# Arduino_Connector.net
KiCad netlist of a schematic drawn in Altium Designer
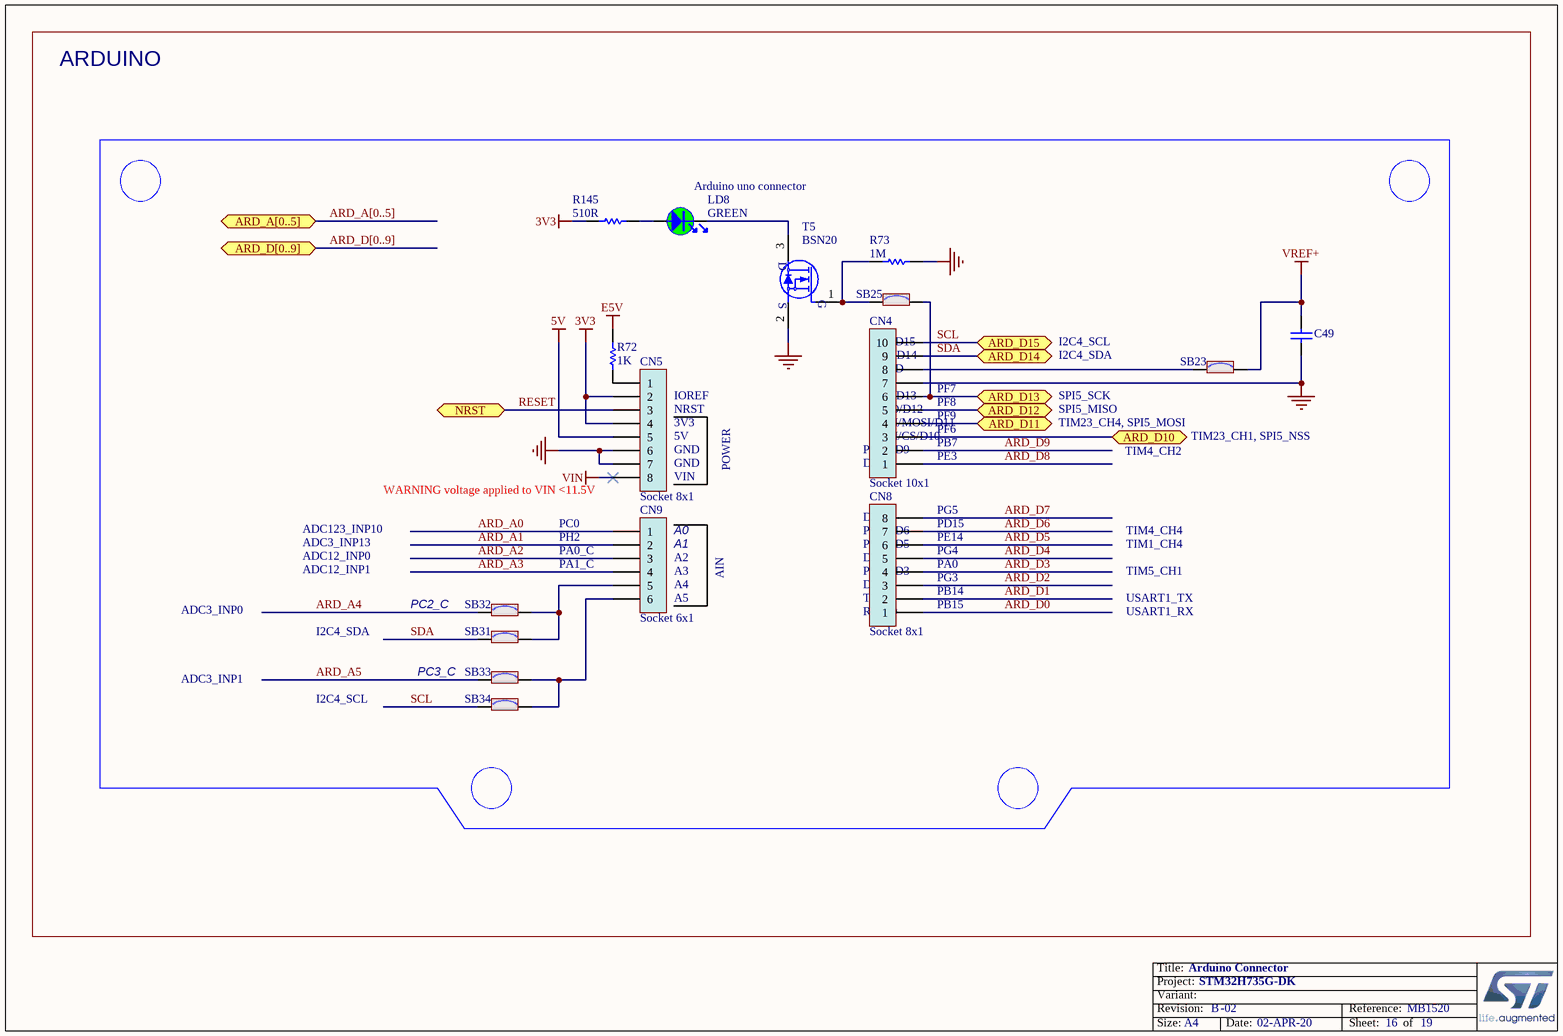
[diagram p0: Arduino Connector.SchDoc]

(export (version "E")
  (design (tool "Eeschema 10.0.6"))
  (components
    (comp (ref "C49")
      (value "Capacitor")
      (footprint "C0603")
      (description "Capacitor, MLCC, 100nF, 16V, X7R, 10%, 0603, T=0,8mm")
      (fields
        (field (name "INTERNAL_PART_NUMBER") "MCD-00211")
        (field (name "MANUFACTURER_PART_NUMBER") "CC0603KRX7R7BB104")
        (field (name "PROVIDED_BY") "SUBCO")
      )
      (libsource (lib "MCD_PARTS_database") (part "Capacitor"))
    )
    (comp (ref "CN4")
      (value "Socket 10x1")
      (footprint "CON_SAMTEC_SSW-110-22-X-S-VS")
      (description "Socket, 10x1, 2.54mm, VR, SMT, Height 9.78mm")
      (fields
        (field (name "INTERNAL_PART_NUMBER") "MCD-00301")
        (field (name "MANUFACTURER_PART_NUMBER") "SSW-110-22-L-S-VS")
        (field (name "PROVIDED_BY") "SUBCO")
      )
      (libsource (lib "MCD_PARTS_database") (part "Socket 10x1"))
    )
    (comp (ref "CN5")
      (value "Socket 8x1")
      (footprint "CON_SAMTEC_SSW-108-22-X-S-VS")
      (description "Socket, 8x1, 2.54mm, VR, SMT, Height 9.78mm")
      (fields
        (field (name "INTERNAL_PART_NUMBER") "MCD-00300")
        (field (name "MANUFACTURER_PART_NUMBER") "SSW-108-22-L-S-VS")
        (field (name "PROVIDED_BY") "SUBCO")
      )
      (libsource (lib "MCD_PARTS_database") (part "Socket 8x1"))
    )
    (comp (ref "CN8")
      (value "Socket 8x1")
      (footprint "CON_SAMTEC_SSW-108-22-X-S-VS")
      (description "Socket, 8x1, 2.54mm, VR, SMT, Height 9.78mm")
      (fields
        (field (name "INTERNAL_PART_NUMBER") "MCD-00300")
        (field (name "MANUFACTURER_PART_NUMBER") "SSW-108-22-L-S-VS")
        (field (name "PROVIDED_BY") "SUBCO")
      )
      (libsource (lib "") (part "Socket 8x1_1"))
    )
    (comp (ref "CN9")
      (value "Socket 6x1")
      (footprint "CON_SAMTEC_SSW-106-22-X-S-VS")
      (description "Socket, 6x1, 2.54mm, VR, SMT, Height 9.78mm")
      (fields
        (field (name "INTERNAL_PART_NUMBER") "MCD-00299")
        (field (name "MANUFACTURER_PART_NUMBER") "SSW-106-22-L-S-VS")
        (field (name "PROVIDED_BY") "SUBCO")
      )
      (libsource (lib "MCD_PARTS_database") (part "Socket 6x1"))
    )
    (comp (ref "LD8")
      (value "GREEN")
      (footprint "LED_0603_GREEN")
      (description "LED, Green, 0603")
      (fields
        (field (name "INTERNAL_PART_NUMBER") "MCD-00050")
        (field (name "MANUFACTURER_PART_NUMBER") "19-213SYGC/S530-E2/TR8")
        (field (name "PROVIDED_BY") "SUBCO")
      )
      (libsource (lib "MCD_PARTS_database") (part "LED_green"))
    )
    (comp (ref "R72")
      (value "1K")
      (footprint "R0603")
      (description "Resistor,1K,0603,1%,1/10W")
      (fields
        (field (name "INTERNAL_PART_NUMBER") "MCD-00070")
        (field (name "MANUFACTURER_PART_NUMBER") "RC0603FR-071KL")
        (field (name "PROVIDED_BY") "SUBCO")
      )
      (libsource (lib "MCD_PARTS_database") (part "Resistor"))
    )
    (comp (ref "R73")
      (value "1M")
      (footprint "R0603")
      (description "Resistor,1M,0603,1%,1/10W")
      (fields
        (field (name "INTERNAL_PART_NUMBER") "MCD-00257")
        (field (name "MANUFACTURER_PART_NUMBER") "RC0603FR-071ML")
        (field (name "PROVIDED_BY") "SUBCO")
      )
      (libsource (lib "MCD_PARTS_database") (part "Resistor"))
    )
    (comp (ref "R145")
      (value "510R")
      (footprint "R0603")
      (description "Resistor,510R,0603,1%,1/10W")
      (fields
        (field (name "INTERNAL_PART_NUMBER") "MCD-00225")
        (field (name "MANUFACTURER_PART_NUMBER") "RC0603FR-07510RL")
        (field (name "PROVIDED_BY") "SUBCO")
      )
      (libsource (lib "MCD_PARTS_database") (part "Resistor"))
    )
    (comp (ref "SB23")
      (value "SB_ON")
      (footprint "SOLDER-BRIDGE_R0603-0R")
      (description "Solder Bridge ON")
      (fields
        (field (name "INTERNAL_PART_NUMBER") "MCD-00071")
        (field (name "MANUFACTURER_PART_NUMBER") "RC0603JR-070RL")
        (field (name "PROVIDED_BY") "SUBCO")
      )
      (libsource (lib "MCD_PARTS_database") (part "SB_ON"))
    )
    (comp (ref "SB25")
      (value "SB_ON")
      (footprint "SOLDER-BRIDGE_R0603-0R")
      (description "Solder Bridge ON")
      (fields
        (field (name "INTERNAL_PART_NUMBER") "MCD-00071")
        (field (name "MANUFACTURER_PART_NUMBER") "RC0603JR-070RL")
        (field (name "PROVIDED_BY") "SUBCO")
      )
      (libsource (lib "MCD_PARTS_database") (part "SB_ON"))
    )
    (comp (ref "SB31")
      (value "SB_ON")
      (footprint "SOLDER-BRIDGE_R0603-0R")
      (description "Solder Bridge ON")
      (fields
        (field (name "INTERNAL_PART_NUMBER") "MCD-00071")
        (field (name "MANUFACTURER_PART_NUMBER") "RC0603JR-070RL")
        (field (name "PROVIDED_BY") "SUBCO")
      )
      (libsource (lib "MCD_PARTS_database") (part "SB_ON"))
    )
    (comp (ref "SB32")
      (value "SB_ON")
      (footprint "SOLDER-BRIDGE_R0603-0R")
      (description "Solder Bridge ON")
      (fields
        (field (name "INTERNAL_PART_NUMBER") "MCD-00071")
        (field (name "MANUFACTURER_PART_NUMBER") "RC0603JR-070RL")
        (field (name "PROVIDED_BY") "SUBCO")
      )
      (libsource (lib "MCD_PARTS_database") (part "SB_ON"))
    )
    (comp (ref "SB33")
      (value "SB_ON")
      (footprint "SOLDER-BRIDGE_R0603-0R")
      (description "Solder Bridge ON")
      (fields
        (field (name "INTERNAL_PART_NUMBER") "MCD-00071")
        (field (name "MANUFACTURER_PART_NUMBER") "RC0603JR-070RL")
        (field (name "PROVIDED_BY") "SUBCO")
      )
      (libsource (lib "MCD_PARTS_database") (part "SB_ON"))
    )
    (comp (ref "SB34")
      (value "SB_ON")
      (footprint "SOLDER-BRIDGE_R0603-0R")
      (description "Solder Bridge ON")
      (fields
        (field (name "INTERNAL_PART_NUMBER") "MCD-00071")
        (field (name "MANUFACTURER_PART_NUMBER") "RC0603JR-070RL")
        (field (name "PROVIDED_BY") "SUBCO")
      )
      (libsource (lib "MCD_PARTS_database") (part "SB_ON"))
    )
    (comp (ref "T5")
      (value "BSN20")
      (footprint "MOS_SOT23")
      (description "N-channel enhancement mode field-effect transistor")
      (fields
        (field (name "INTERNAL_PART_NUMBER") "MCD-00151")
        (field (name "MANUFACTURER") "NXP")
        (field (name "PROVIDED_BY") "SUBCO")
      )
      (libsource (lib "MCD_PARTS_database") (part "BSN20"))
    )
  )
  (nets
    (net (code "1") (name "/ARD_A0") (class "Default")
      (node (ref "CN9") (pin "1") (pinfunction "1_1") (pintype "passive"))
    )
    (net (code "2") (name "/ARD_A1") (class "Default")
      (node (ref "CN9") (pin "2") (pinfunction "2_2") (pintype "passive"))
    )
    (net (code "3") (name "/ARD_A2") (class "Default")
      (node (ref "CN9") (pin "3") (pinfunction "3_3") (pintype "passive"))
    )
    (net (code "4") (name "/ARD_A3") (class "Default")
      (node (ref "CN9") (pin "4") (pinfunction "4_4") (pintype "passive"))
    )
    (net (code "5") (name "/ARD_A4") (class "Default")
      (node (ref "SB32") (pin "1") (pinfunction "1_1") (pintype "passive"))
    )
    (net (code "6") (name "/ARD_A5") (class "Default")
      (node (ref "SB33") (pin "1") (pinfunction "1_1") (pintype "passive"))
    )
    (net (code "8") (name "/ARD_D0") (class "Default")
      (node (ref "CN8") (pin "1") (pinfunction "1_1") (pintype "passive"))
    )
    (net (code "9") (name "/ARD_D1") (class "Default")
      (node (ref "CN8") (pin "2") (pinfunction "2_2") (pintype "passive"))
    )
    (net (code "10") (name "/ARD_D2") (class "Default")
      (node (ref "CN8") (pin "3") (pinfunction "3_3") (pintype "passive"))
    )
    (net (code "11") (name "/ARD_D3") (class "Default")
      (node (ref "CN8") (pin "4") (pinfunction "4_4") (pintype "passive"))
    )
    (net (code "12") (name "/ARD_D4") (class "Default")
      (node (ref "CN8") (pin "5") (pinfunction "5_5") (pintype "passive"))
    )
    (net (code "13") (name "/ARD_D5") (class "Default")
      (node (ref "CN8") (pin "6") (pinfunction "6_6") (pintype "passive"))
    )
    (net (code "14") (name "/ARD_D6") (class "Default")
      (node (ref "CN8") (pin "7") (pinfunction "7_7") (pintype "passive"))
    )
    (net (code "15") (name "/ARD_D7") (class "Default")
      (node (ref "CN8") (pin "8") (pinfunction "8_8") (pintype "passive"))
    )
    (net (code "16") (name "/ARD_D8") (class "Default")
      (node (ref "CN4") (pin "1") (pinfunction "1_1") (pintype "passive"))
    )
    (net (code "17") (name "/ARD_D9") (class "Default")
      (node (ref "CN4") (pin "2") (pinfunction "2_2") (pintype "passive"))
    )
    (net (code "18") (name "/ARD_D10") (class "Default")
      (node (ref "CN4") (pin "3") (pinfunction "3_3") (pintype "passive"))
    )
    (net (code "19") (name "/ARD_D11") (class "Default")
      (node (ref "CN4") (pin "4") (pinfunction "4_4") (pintype "passive"))
    )
    (net (code "20") (name "/ARD_D12") (class "Default")
      (node (ref "CN4") (pin "5") (pinfunction "5_5") (pintype "passive"))
    )
    (net (code "21") (name "/ARD_D13") (class "Default")
      (node (ref "CN4") (pin "6") (pinfunction "6_6") (pintype "passive"))
      (node (ref "SB25") (pin "2") (pinfunction "2_2") (pintype "passive"))
    )
    (net (code "23") (name "/RESET") (class "Default")
      (node (ref "CN5") (pin "3") (pinfunction "3_3") (pintype "passive"))
    )
    (net (code "24") (name "/SCL") (class "Default")
      (node (ref "CN4") (pin "10") (pinfunction "10_10") (pintype "passive"))
      (node (ref "SB34") (pin "1") (pinfunction "1_1") (pintype "passive"))
    )
    (net (code "25") (name "/SDA") (class "Default")
      (node (ref "CN4") (pin "9") (pinfunction "9_9") (pintype "passive"))
      (node (ref "SB31") (pin "1") (pinfunction "1_1") (pintype "passive"))
    )
    (net (code "26") (name "3V3") (class "Default")
      (node (ref "CN5") (pin "2") (pinfunction "2_2") (pintype "passive"))
      (node (ref "CN5") (pin "4") (pinfunction "4_4") (pintype "passive"))
      (node (ref "R145") (pin "2") (pinfunction "2_2") (pintype "passive"))
    )
    (net (code "27") (name "5V") (class "Default")
      (node (ref "CN5") (pin "5") (pinfunction "5_5") (pintype "passive"))
    )
    (net (code "28") (name "E5V") (class "Default")
      (node (ref "R72") (pin "1") (pinfunction "1_1") (pintype "passive"))
    )
    (net (code "29") (name "GND") (class "Default")
      (node (ref "C49") (pin "1") (pinfunction "1_1") (pintype "passive"))
      (node (ref "CN4") (pin "7") (pinfunction "7_7") (pintype "passive"))
      (node (ref "CN5") (pin "6") (pinfunction "6_6") (pintype "passive"))
      (node (ref "CN5") (pin "7") (pinfunction "7_7") (pintype "passive"))
      (node (ref "R73") (pin "2") (pinfunction "2_2") (pintype "passive"))
      (node (ref "T5") (pin "2") (pinfunction "S_2") (pintype "passive"))
    )
    (net (code "30") (name "Net-(CN4-Pad8)") (class "Default")
      (node (ref "CN4") (pin "8") (pinfunction "8_8") (pintype "passive"))
      (node (ref "SB23") (pin "1") (pinfunction "1_1") (pintype "passive"))
    )
    (net (code "31") (name "Net-(CN5-Pad1)") (class "Default")
      (node (ref "CN5") (pin "1") (pinfunction "1_1") (pintype "passive"))
      (node (ref "R72") (pin "2") (pinfunction "2_2") (pintype "passive"))
    )
    (net (code "32") (name "Net-(CN9-Pad5)") (class "Default")
      (node (ref "CN9") (pin "5") (pinfunction "5_5") (pintype "passive"))
      (node (ref "SB31") (pin "2") (pinfunction "2_2") (pintype "passive"))
      (node (ref "SB32") (pin "2") (pinfunction "2_2") (pintype "passive"))
    )
    (net (code "33") (name "Net-(CN9-Pad6)") (class "Default")
      (node (ref "CN9") (pin "6") (pinfunction "6_6") (pintype "passive"))
      (node (ref "SB33") (pin "2") (pinfunction "2_2") (pintype "passive"))
      (node (ref "SB34") (pin "2") (pinfunction "2_2") (pintype "passive"))
    )
    (net (code "34") (name "Net-(LD8-Pad1)") (class "Default")
      (node (ref "LD8") (pin "1") (pintype "passive"))
      (node (ref "R145") (pin "1") (pinfunction "1_1") (pintype "passive"))
    )
    (net (code "35") (name "Net-(T5-D)") (class "Default")
      (node (ref "LD8") (pin "2") (pintype "passive"))
      (node (ref "T5") (pin "3") (pinfunction "D_3") (pintype "passive"))
    )
    (net (code "36") (name "Net-(T5-G)") (class "Default")
      (node (ref "R73") (pin "1") (pinfunction "1_1") (pintype "passive"))
      (node (ref "SB25") (pin "1") (pinfunction "1_1") (pintype "passive"))
      (node (ref "T5") (pin "1") (pinfunction "G_1") (pintype "passive"))
    )
    (net (code "37") (name "VIN") (class "Default")
      (node (ref "CN5") (pin "8") (pinfunction "8_8") (pintype "passive"))
    )
    (net (code "38") (name "VREF+") (class "Default")
      (node (ref "C49") (pin "2") (pinfunction "2_2") (pintype "passive"))
      (node (ref "SB23") (pin "2") (pinfunction "2_2") (pintype "passive"))
    )
  )
)
